# CAN-breakout-v1.net
KiCad netlist of a schematic drawn in EAGLE
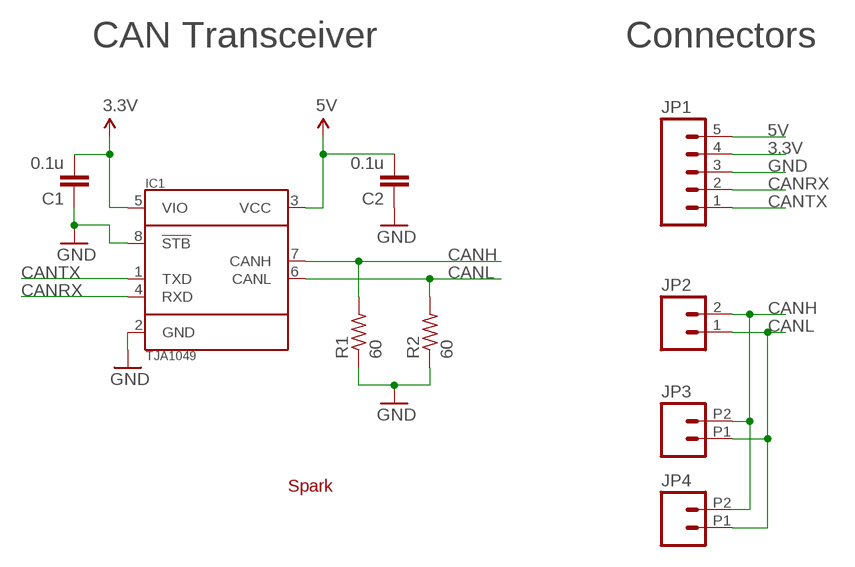
[diagram p0: schematic, sheet 1]

(export (version "E")
  (design (tool "Eeschema 10.0.6"))
  (components
    (comp (ref "C1")
      (value "0.1u")
      (footprint "eagle-import:C1206")
      (fields (field (name "PARTNO") "GRM155R71C104KA88D"))
      (libsource (lib "eagle-import") (part "C-EUC1206"))
    )
    (comp (ref "C2")
      (value "0.1u")
      (footprint "eagle-import:C1206")
      (fields (field (name "PARTNO") "GRM155R71C104KA88D"))
      (libsource (lib "eagle-import") (part "C-EUC1206"))
    )
    (comp (ref "IC1")
      (value "TJA1049")
      (footprint "eagle-import:SO8")
      (fields (field (name "PARTNO") "TJA1049T-118"))
      (libsource (lib "eagle-import") (part "TJA1049"))
    )
    (comp (ref "JP1")
      (value "M05PTH")
      (footprint "eagle-import:1X05")
      (fields (field (name "PARTNO") "PREC005SAAN-RC"))
      (libsource (lib "eagle-import") (part "M05PTH"))
    )
    (comp (ref "JP2")
      (value "M02PTH")
      (footprint "eagle-import:1X02")
      (fields (field (name "PARTNO") "PREC002SAAN-RC"))
      (libsource (lib "eagle-import") (part "M02PTH"))
    )
    (comp (ref "JP3")
      (value "M022.54MM_SCREWTERM")
      (footprint "eagle-import:1X02_2.54_SCREWTERM")
      (fields (field (name "PARTNO") "OSTVN02A150"))
      (libsource (lib "eagle-import") (part "M022.54MM_SCREWTERM"))
    )
    (comp (ref "JP4")
      (value "M022.54MM_SCREWTERM")
      (footprint "eagle-import:1X02_2.54_SCREWTERM")
      (fields (field (name "PARTNO") "OSTVN02A150"))
      (libsource (lib "eagle-import") (part "M022.54MM_SCREWTERM"))
    )
    (comp (ref "R1")
      (value "60")
      (footprint "eagle-import:R1206")
      (fields (field (name "PARTNO") "ERJ-2RKF6202X"))
      (libsource (lib "eagle-import") (part "R-US_R1206"))
    )
    (comp (ref "R2")
      (value "60")
      (footprint "eagle-import:R1206")
      (fields (field (name "PARTNO") "ERJ-2RKF1002X"))
      (libsource (lib "eagle-import") (part "R-US_R1206"))
    )
    (comp (ref "U$3")
      (value "SPARK_LOGO2")
      (footprint "eagle-import:SPARK_LOGO2")
      (libsource (lib "eagle-import") (part "SPARK_LOGO2"))
    )
  )
  (nets
    (net (code "1") (name "/CANH") (class "Default")
      (node (ref "IC1") (pin "7") (pinfunction "CANH_7") (pintype "bidirectional"))
      (node (ref "JP2") (pin "2") (pinfunction "2_2") (pintype "passive"))
      (node (ref "JP3") (pin "P2") (pinfunction "2_P2") (pintype "passive"))
      (node (ref "JP4") (pin "P2") (pinfunction "2_P2") (pintype "passive"))
      (node (ref "R1") (pin "2") (pinfunction "2_2") (pintype "passive"))
    )
    (net (code "2") (name "/CANL") (class "Default")
      (node (ref "IC1") (pin "6") (pinfunction "CANL_6") (pintype "bidirectional"))
      (node (ref "JP2") (pin "1") (pinfunction "1_1") (pintype "passive"))
      (node (ref "JP3") (pin "P1") (pinfunction "1_P1") (pintype "passive"))
      (node (ref "JP4") (pin "P1") (pinfunction "1_P1") (pintype "passive"))
      (node (ref "R2") (pin "2") (pinfunction "2_2") (pintype "passive"))
    )
    (net (code "3") (name "/CANRX") (class "Default")
      (node (ref "IC1") (pin "4") (pinfunction "RXD_4") (pintype "bidirectional"))
      (node (ref "JP1") (pin "2") (pinfunction "2_2") (pintype "passive"))
    )
    (net (code "4") (name "/CANTX") (class "Default")
      (node (ref "IC1") (pin "1") (pinfunction "TXD_1") (pintype "bidirectional"))
      (node (ref "JP1") (pin "1") (pinfunction "1_1") (pintype "passive"))
    )
    (net (code "5") (name "3.3V") (class "Default")
      (node (ref "C1") (pin "2") (pinfunction "2_2") (pintype "passive"))
      (node (ref "IC1") (pin "5") (pinfunction "VIO_5") (pintype "bidirectional"))
      (node (ref "JP1") (pin "4") (pinfunction "4_4") (pintype "passive"))
    )
    (net (code "6") (name "5V") (class "Default")
      (node (ref "C2") (pin "2") (pinfunction "2_2") (pintype "passive"))
      (node (ref "IC1") (pin "3") (pinfunction "VCC_3") (pintype "bidirectional"))
      (node (ref "JP1") (pin "5") (pinfunction "5_5") (pintype "passive"))
    )
    (net (code "7") (name "GND") (class "Default")
      (node (ref "C1") (pin "1") (pinfunction "1_1") (pintype "passive"))
      (node (ref "C2") (pin "1") (pinfunction "1_1") (pintype "passive"))
      (node (ref "IC1") (pin "2") (pinfunction "GND_2") (pintype "bidirectional"))
      (node (ref "IC1") (pin "8") (pinfunction "~{STB}_8") (pintype "bidirectional"))
      (node (ref "JP1") (pin "3") (pinfunction "3_3") (pintype "passive"))
      (node (ref "R1") (pin "1") (pinfunction "1_1") (pintype "passive"))
      (node (ref "R2") (pin "1") (pinfunction "1_1") (pintype "passive"))
    )
  )
)
